# LM2623.net
KiCad netlist of a schematic drawn in EAGLE
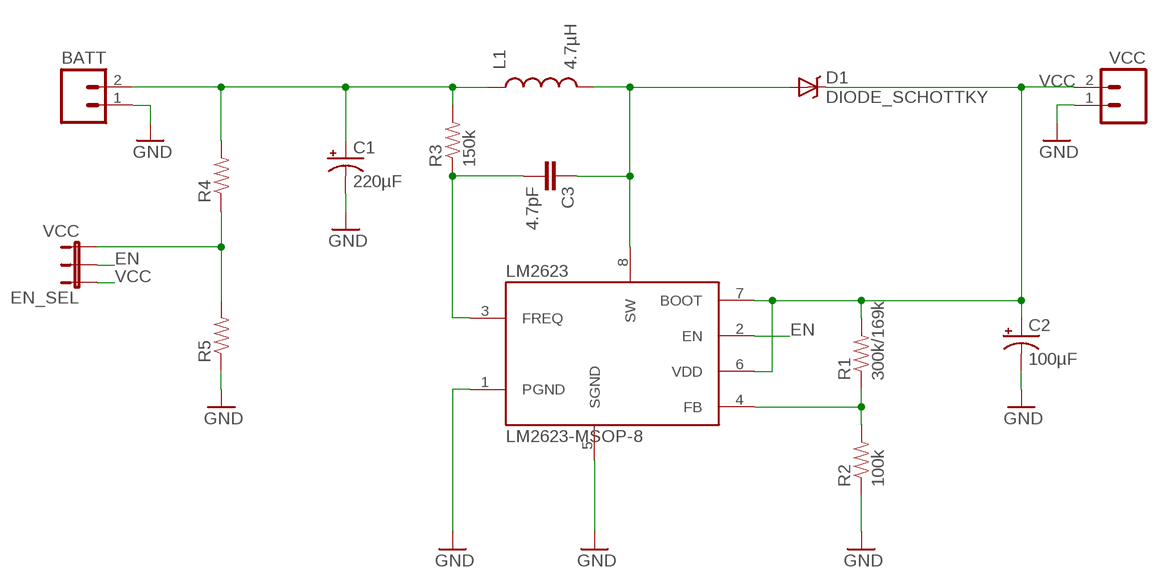
[diagram p0: schematic, sheet 1]

(export (version "E")
  (design (tool "Eeschema 10.0.6"))
  (components
    (comp (ref "BATT")
      (value "M02PTH")
      (footprint "eagle-import:1X02")
      (libsource (lib "eagle-import") (part "M02PTH"))
    )
    (comp (ref "C1")
      (value "220µF")
      (footprint "eagle-import:EIA3528")
      (libsource (lib "eagle-import") (part "CAP_POL3528"))
    )
    (comp (ref "C2")
      (value "100µF")
      (footprint "eagle-import:EIA3528")
      (libsource (lib "eagle-import") (part "CAP_POL3528"))
    )
    (comp (ref "C3")
      (value "4.7pF")
      (footprint "eagle-import:0603-CAP")
      (libsource (lib "eagle-import") (part "CAP0603-CAP"))
    )
    (comp (ref "D1")
      (value "DIODE_SCHOTTKY")
      (footprint "eagle-import:DO-214AB")
      (libsource (lib "eagle-import") (part "DIODE_SCHOTTKY"))
    )
    (comp (ref "EN_SEL")
      (value "VCC")
      (footprint "eagle-import:SJ_3")
      (libsource (lib "eagle-import") (part "JUMPER-3SMD"))
    )
    (comp (ref "L1")
      (value "4.7µH")
      (footprint "eagle-import:INDUCTOR_SRR7032")
      (libsource (lib "eagle-import") (part "INDUCTOR-SRR7032"))
    )
    (comp (ref "LM2623")
      (value "LM2623-MSOP-8")
      (footprint "eagle-import:MSOP-8")
      (libsource (lib "eagle-import") (part "LM2623-MSOP-8"))
    )
    (comp (ref "R1")
      (value "300k/169k")
      (footprint "eagle-import:0805")
      (libsource (lib "eagle-import") (part "RESISTOR0805-RES"))
    )
    (comp (ref "R2")
      (value "100k")
      (footprint "eagle-import:0805")
      (libsource (lib "eagle-import") (part "RESISTOR0805-RES"))
    )
    (comp (ref "R3")
      (value "150k")
      (footprint "eagle-import:0805")
      (libsource (lib "eagle-import") (part "RESISTOR0805-RES"))
    )
    (comp (ref "R4")
      (value "RESISTOR0805-RES")
      (footprint "eagle-import:0805")
      (libsource (lib "eagle-import") (part "RESISTOR0805-RES"))
    )
    (comp (ref "R5")
      (value "RESISTOR0805-RES")
      (footprint "eagle-import:0805")
      (libsource (lib "eagle-import") (part "RESISTOR0805-RES"))
    )
    (comp (ref "VCC")
      (value "M02PTH")
      (footprint "eagle-import:1X02")
      (libsource (lib "eagle-import") (part "M02PTH"))
    )
  )
  (nets
    (net (code "1") (name "/EN") (class "Default")
      (node (ref "EN_SEL") (pin "2") (pinfunction "2_2") (pintype "passive"))
      (node (ref "LM2623") (pin "2") (pinfunction "EN_2") (pintype "bidirectional"))
    )
    (net (code "2") (name "/VCC") (class "Default")
      (node (ref "C2") (pin "A") (pinfunction "+_A") (pintype "passive"))
      (node (ref "D1") (pin "C") (pinfunction "C_C") (pintype "passive"))
      (node (ref "EN_SEL") (pin "1") (pinfunction "1_1") (pintype "passive"))
      (node (ref "LM2623") (pin "6") (pinfunction "VDD_6") (pintype "bidirectional"))
      (node (ref "LM2623") (pin "7") (pinfunction "BOOT_7") (pintype "bidirectional"))
      (node (ref "R1") (pin "2") (pinfunction "2_2") (pintype "passive"))
      (node (ref "VCC") (pin "2") (pinfunction "2_2") (pintype "passive"))
    )
    (net (code "3") (name "GND") (class "Default")
      (node (ref "BATT") (pin "1") (pinfunction "1_1") (pintype "passive"))
      (node (ref "C1") (pin "C") (pinfunction "-_C") (pintype "passive"))
      (node (ref "C2") (pin "C") (pinfunction "-_C") (pintype "passive"))
      (node (ref "LM2623") (pin "1") (pinfunction "PGND_1") (pintype "bidirectional"))
      (node (ref "LM2623") (pin "5") (pinfunction "SGND_5") (pintype "bidirectional"))
      (node (ref "R2") (pin "1") (pinfunction "1_1") (pintype "passive"))
      (node (ref "R5") (pin "1") (pinfunction "1_1") (pintype "passive"))
      (node (ref "VCC") (pin "1") (pinfunction "1_1") (pintype "passive"))
    )
    (net (code "4") (name "Net-(C1-+)") (class "Default")
      (node (ref "BATT") (pin "2") (pinfunction "2_2") (pintype "passive"))
      (node (ref "C1") (pin "A") (pinfunction "+_A") (pintype "passive"))
      (node (ref "L1") (pin "2") (pinfunction "2_2") (pintype "passive"))
      (node (ref "R3") (pin "2") (pinfunction "2_2") (pintype "passive"))
      (node (ref "R4") (pin "2") (pinfunction "2_2") (pintype "passive"))
    )
    (net (code "5") (name "Net-(EN_SEL-Pad3)") (class "Default")
      (node (ref "EN_SEL") (pin "3") (pinfunction "3_3") (pintype "passive"))
      (node (ref "R4") (pin "1") (pinfunction "1_1") (pintype "passive"))
      (node (ref "R5") (pin "2") (pinfunction "2_2") (pintype "passive"))
    )
    (net (code "6") (name "Net-(LM2623-FB)") (class "Default")
      (node (ref "LM2623") (pin "4") (pinfunction "FB_4") (pintype "bidirectional"))
      (node (ref "R1") (pin "1") (pinfunction "1_1") (pintype "passive"))
      (node (ref "R2") (pin "2") (pinfunction "2_2") (pintype "passive"))
    )
    (net (code "7") (name "Net-(LM2623-FREQ)") (class "Default")
      (node (ref "C3") (pin "2") (pinfunction "2_2") (pintype "passive"))
      (node (ref "LM2623") (pin "3") (pinfunction "FREQ_3") (pintype "bidirectional"))
      (node (ref "R3") (pin "1") (pinfunction "1_1") (pintype "passive"))
    )
    (net (code "8") (name "Net-(LM2623-SW)") (class "Default")
      (node (ref "C3") (pin "1") (pinfunction "1_1") (pintype "passive"))
      (node (ref "D1") (pin "A") (pinfunction "A_A") (pintype "passive"))
      (node (ref "L1") (pin "1") (pinfunction "1_1") (pintype "passive"))
      (node (ref "LM2623") (pin "8") (pinfunction "SW_8") (pintype "bidirectional"))
    )
  )
)
